# Arduino_MEGA_2560-Rev3.net
KiCad netlist of a schematic drawn in Altium Designer
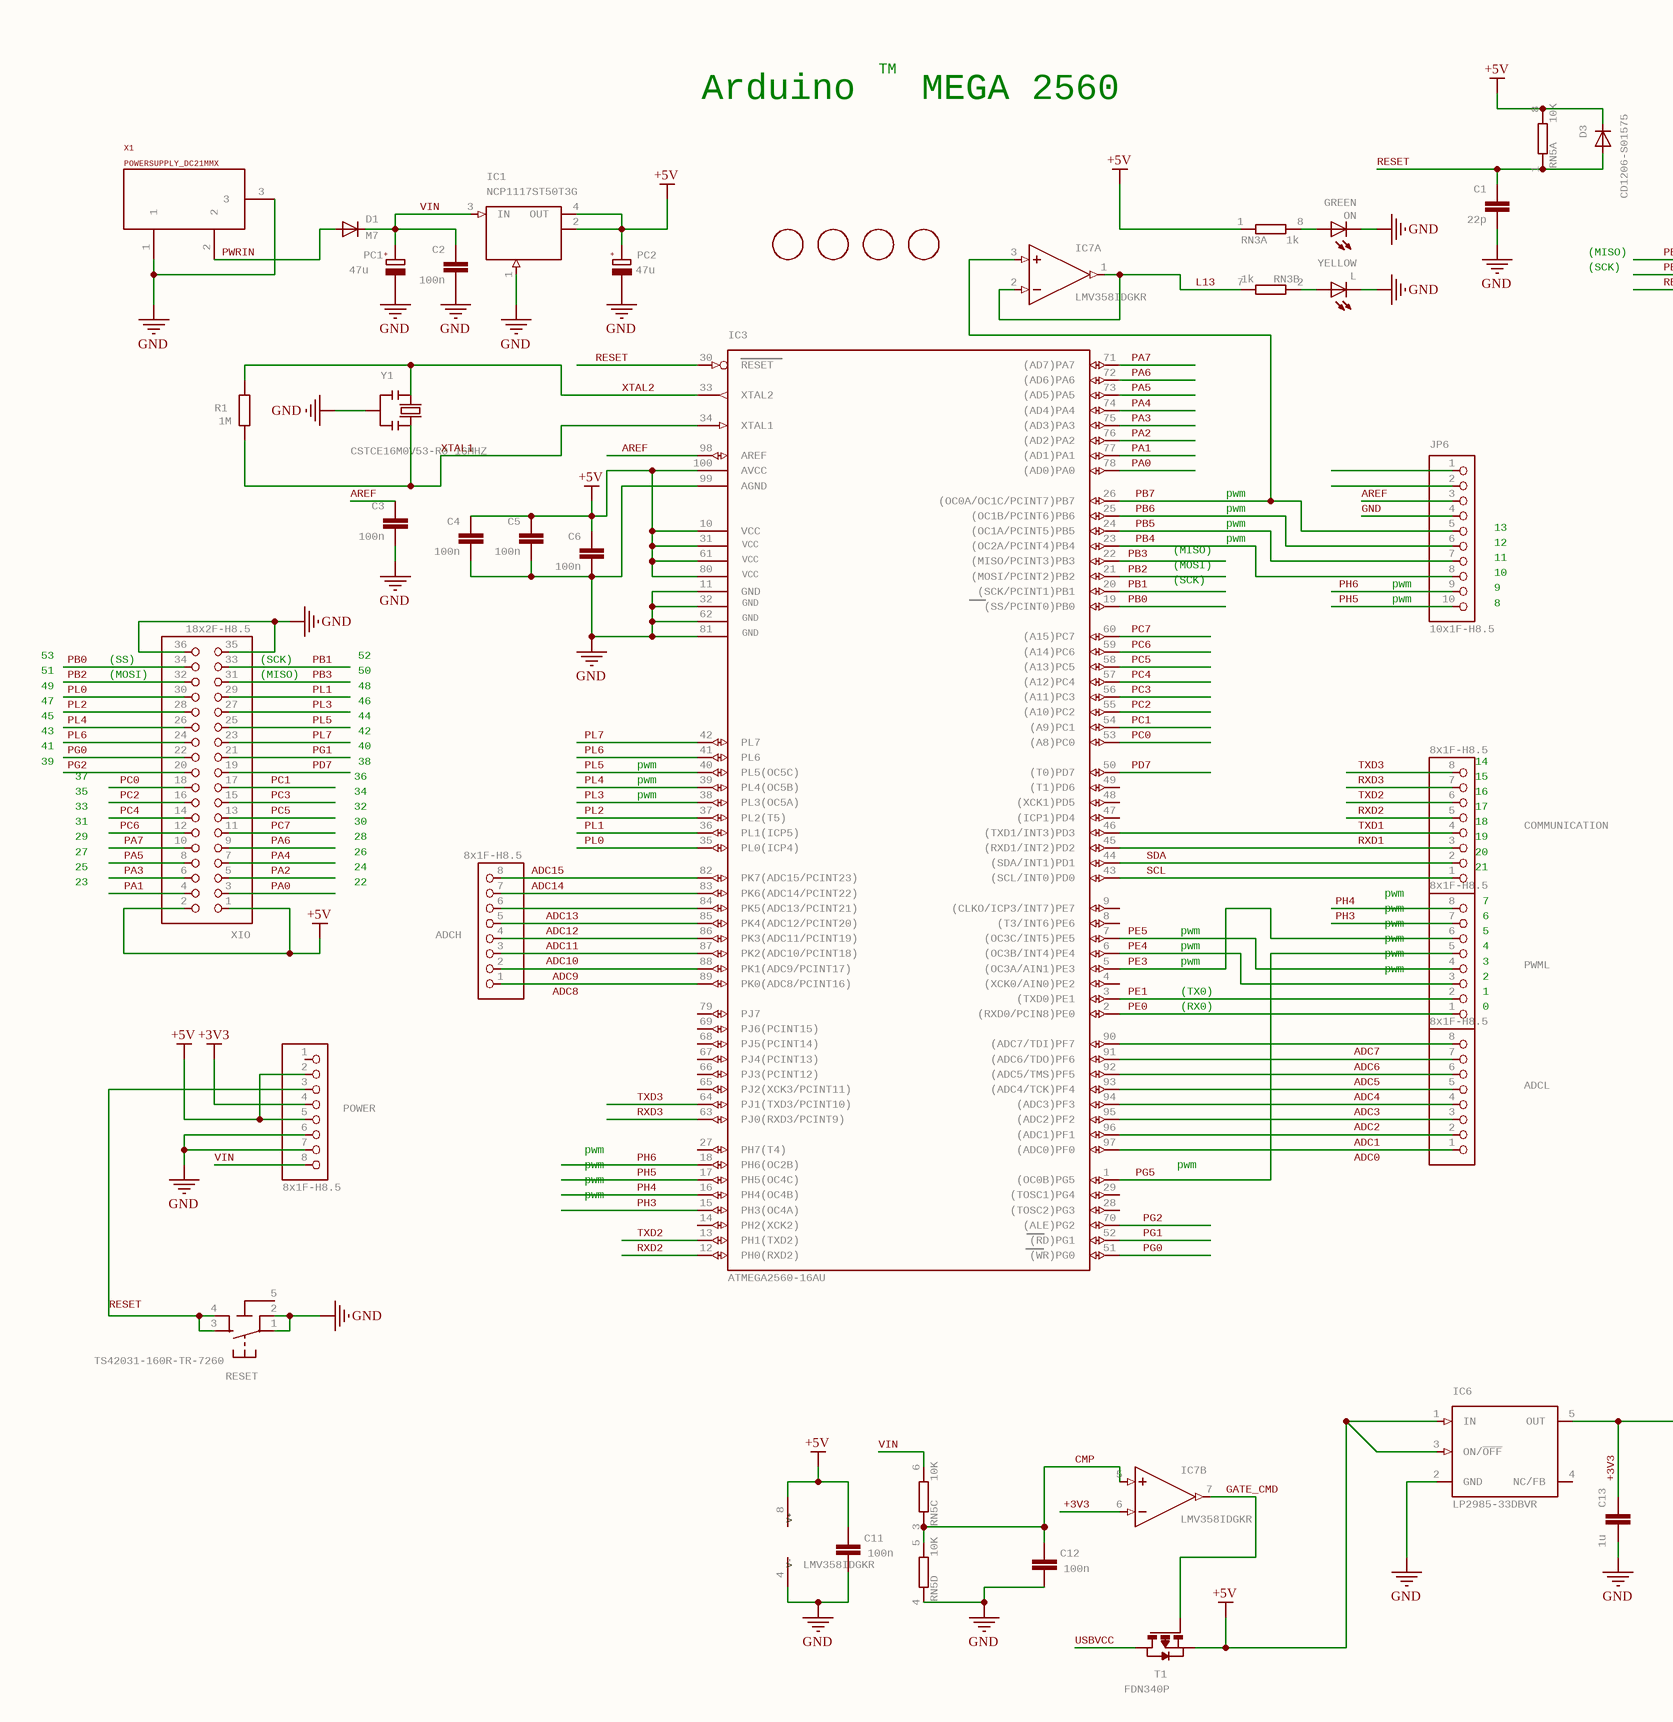
[diagram p0: Arduino_MEGA_2560-Rev3.SchDoc, left]
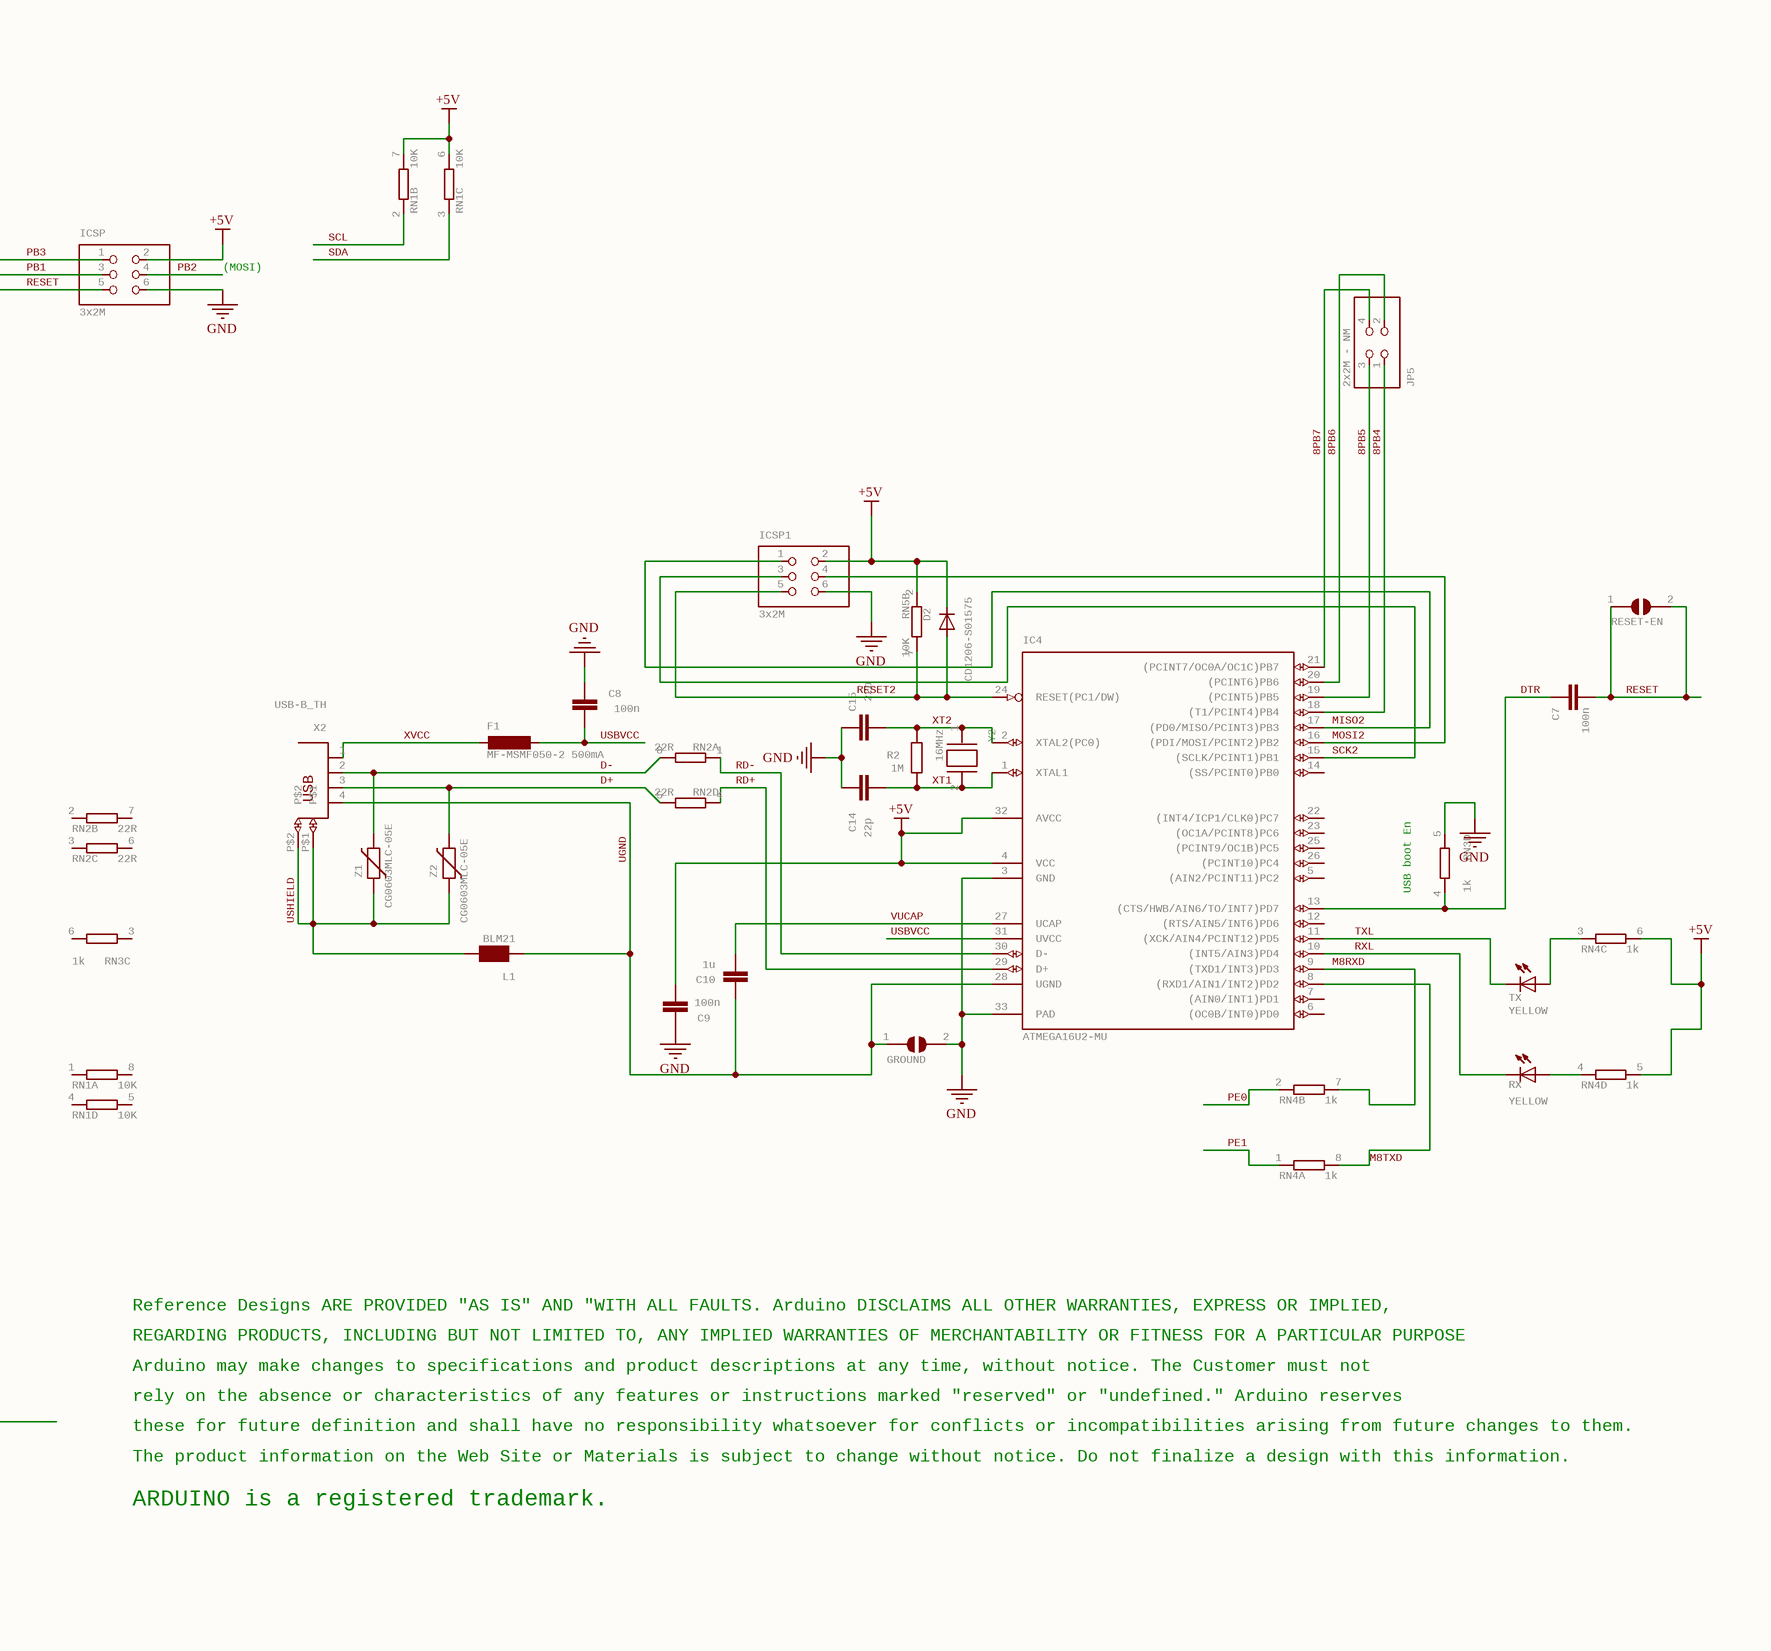
[diagram p1: Arduino_MEGA_2560-Rev3.SchDoc, right]

(export (version "E")
  (design (tool "Eeschema 10.0.6"))
  (components
    (comp (ref "ADCH")
      (value "8x1F-H8.5")
      (footprint "1X08")
      (description "PIN HEADER")
      (libsource (lib "SmartPrj") (part "PINHD-1X8"))
    )
    (comp (ref "ADCL")
      (value "8x1F-H8.5")
      (footprint "1X08")
      (description "PIN HEADER")
      (libsource (lib "SmartPrj") (part "PINHD-1X8"))
    )
    (comp (ref "C1")
      (value "22p")
      (footprint "C0603-ROUND")
      (description "CAPACITOR, European symbol")
      (libsource (lib "SmartPrj") (part "C-EU0603-RND"))
    )
    (comp (ref "C2")
      (value "100n")
      (footprint "C0603-ROUND")
      (description "CAPACITOR, European symbol")
      (libsource (lib "SmartPrj") (part "C-EU0603-RND"))
    )
    (comp (ref "C3")
      (value "100n")
      (footprint "C0603-ROUND")
      (description "CAPACITOR, European symbol")
      (libsource (lib "SmartPrj") (part "C-EU0603-RND"))
    )
    (comp (ref "C4")
      (value "100n")
      (footprint "C0603-ROUND")
      (description "CAPACITOR, European symbol")
      (libsource (lib "SmartPrj") (part "C-EU0603-RND"))
    )
    (comp (ref "C5")
      (value "100n")
      (footprint "C0603-ROUND")
      (description "CAPACITOR, European symbol")
      (libsource (lib "SmartPrj") (part "C-EU0603-RND"))
    )
    (comp (ref "C6")
      (value "100n")
      (footprint "C0603-ROUND")
      (description "CAPACITOR, European symbol")
      (libsource (lib "SmartPrj") (part "C-EU0603-RND"))
    )
    (comp (ref "C7")
      (value "100n")
      (footprint "C0603-ROUND")
      (description "CAPACITOR, European symbol")
      (libsource (lib "") (part "C-EU0603-RND_3"))
    )
    (comp (ref "C8")
      (value "100n")
      (footprint "C0603-ROUND")
      (description "CAPACITOR, European symbol")
      (libsource (lib "") (part "C-EU0603-RND_3"))
    )
    (comp (ref "C9")
      (value "100n")
      (footprint "C0603-ROUND")
      (description "CAPACITOR, European symbol")
      (libsource (lib "") (part "C-EU0603-RND_2"))
    )
    (comp (ref "C10")
      (value "1u")
      (footprint "C0603-ROUND")
      (description "CAPACITOR, European symbol")
      (libsource (lib "SmartPrj") (part "C-EU0603-RND"))
    )
    (comp (ref "C11")
      (value "100n")
      (footprint "C0603-ROUND")
      (description "CAPACITOR, European symbol")
      (libsource (lib "") (part "C-EU0603-RND_1"))
    )
    (comp (ref "C12")
      (value "100n")
      (footprint "C0603-ROUND")
      (description "CAPACITOR, European symbol")
      (libsource (lib "") (part "C-EU0603-RND_1"))
    )
    (comp (ref "C13")
      (value "1u")
      (footprint "C0603-ROUND")
      (description "CAPACITOR, European symbol")
      (libsource (lib "") (part "C-EU0603-RND_3"))
    )
    (comp (ref "C14")
      (value "22p")
      (footprint "C0603-ROUND")
      (description "CAPACITOR, European symbol")
      (libsource (lib "") (part "C-EU0603-RND_2"))
    )
    (comp (ref "C15")
      (value "22p")
      (footprint "C0603-ROUND")
      (description "CAPACITOR, European symbol")
      (libsource (lib "") (part "C-EU0603-RND_2"))
    )
    (comp (ref "COMMUNICATION")
      (value "8x1F-H8.5")
      (footprint "1X08")
      (description "PIN HEADER")
      (libsource (lib "SmartPrj") (part "PINHD-1X8"))
    )
    (comp (ref "D1")
      (value "M7")
      (footprint "SMB")
      (description "DIODE")
      (libsource (lib "diode") (part "DIODE-SMB"))
    )
    (comp (ref "D2")
      (value "CD1206-S01575")
      (footprint "MINIMELF")
      (description "DIODE")
      (libsource (lib "diode") (part "DIODE-MINIMELF"))
    )
    (comp (ref "D3")
      (value "CD1206-S01575")
      (footprint "MINIMELF")
      (description "DIODE")
      (libsource (lib "diode") (part "DIODE-MINIMELF"))
    )
    (comp (ref "F1")
      (value "MF-MSMF050-2 500mA")
      (footprint "L1812")
      (description "INDUCTOR, European symbol")
      (libsource (lib "rcl") (part "L-EUL1812"))
    )
    (comp (ref "FD1")
      (value "FIDUCIALMOUNT")
      (footprint "FIDUCIA-MOUNT")
      (libsource (lib "SmartPrj") (part "FIDUCIALMOUNT"))
    )
    (comp (ref "FD2")
      (value "FIDUCIALMOUNT")
      (footprint "FIDUCIA-MOUNT")
      (libsource (lib "SmartPrj") (part "FIDUCIALMOUNT"))
    )
    (comp (ref "FD3")
      (value "FIDUCIALMOUNT")
      (footprint "FIDUCIA-MOUNT")
      (libsource (lib "SmartPrj") (part "FIDUCIALMOUNT"))
    )
    (comp (ref "FD4")
      (value "FIDUCIALMOUNT")
      (footprint "FIDUCIA-MOUNT")
      (libsource (lib "SmartPrj") (part "FIDUCIALMOUNT"))
    )
    (comp (ref "GROUND")
      (value "SJ")
      (footprint "SJ")
      (description "SMD solder JUMPER")
      (libsource (lib "jumper") (part "SJ"))
    )
    (comp (ref "IC1")
      (value "NCP1117ST50T3G")
      (footprint "SOT223")
      (libsource (lib "linear") (part "MC33269ST*"))
    )
    (comp (ref "IC3")
      (value "ATMEGA2560-16AU")
      (footprint "TQFP100")
      (fields
        (field (name "GND") "GND")
        (field (name "GND_1") "GND")
        (field (name "GND_2") "GND")
        (field (name "VCC") "VCC")
        (field (name "VCC_1") "VCC")
        (field (name "VCC_2") "VCC")
      )
      (libsource (lib "SmartPrj") (part "ATMEGA2560AU"))
    )
    (comp (ref "IC4")
      (value "ATMEGA16U2-MU")
      (footprint "MLF32")
      (libsource (lib "SmartPrj") (part "ATMEGA16U2-MU"))
    )
    (comp (ref "IC6")
      (value "LP2985-33DBVR")
      (footprint "SOT23-DBV")
      (libsource (lib "SmartPrj") (part "LP2985-XXDBVR"))
    )
    (comp (ref "IC7")
      (value "LMV358IDGKR")
      (footprint "MSOP08")
      (fields (field (name "V+") "V+") (field (name "V-") "V-"))
      (libsource (lib "linear") (part "LMV358?*MM"))
    )
    (comp (ref "ICSP")
      (value "3x2M")
      (footprint "2X03")
      (description "PIN HEADER")
      (libsource (lib "SmartPrj") (part "PINHD-2X3"))
    )
    (comp (ref "ICSP1")
      (value "3x2M")
      (footprint "2X03")
      (description "PIN HEADER")
      (libsource (lib "SmartPrj") (part "PINHD-2X3"))
    )
    (comp (ref "JP5")
      (value "2x2M - NM")
      (footprint "2X02")
      (description "PIN HEADER")
      (libsource (lib "SmartPrj") (part "PINHD-2X2"))
    )
    (comp (ref "JP6")
      (value "10x1F-H8.5")
      (footprint "1X10")
      (description "PIN HEADER")
      (libsource (lib "SmartPrj") (part "PINHD-1X10_ARD"))
    )
    (comp (ref "L")
      (value "YELLOW")
      (footprint "CHIP-LED0805")
      (libsource (lib "led") (part "LEDCHIP-LED0805"))
    )
    (comp (ref "L1")
      (value "BLM21")
      (footprint "0805")
      (libsource (lib "wuerth-elektronik") (part "WE-CBF_0805"))
    )
    (comp (ref "ON")
      (value "GREEN")
      (footprint "CHIP-LED0805")
      (libsource (lib "led") (part "LEDCHIP-LED0805"))
    )
    (comp (ref "PC1")
      (value "47u")
      (footprint "PANASONIC_D")
      (description "POLARIZED CAPACITOR, European symbol")
      (fields (field (name "+") "+"))
      (libsource (lib "rcl") (part "CPOL-EUD"))
    )
    (comp (ref "PC2")
      (value "47u")
      (footprint "PANASONIC_D")
      (description "POLARIZED CAPACITOR, European symbol")
      (fields (field (name "+") "+"))
      (libsource (lib "rcl") (part "CPOL-EUD"))
    )
    (comp (ref "POWER")
      (value "8x1F-H8.5")
      (footprint "1X08")
      (description "PIN HEADER")
      (libsource (lib "SmartPrj") (part "PINHD-1X8"))
    )
    (comp (ref "PWML")
      (value "8x1F-H8.5")
      (footprint "1X08")
      (description "PIN HEADER")
      (libsource (lib "SmartPrj") (part "PINHD-1X8"))
    )
    (comp (ref "R1")
      (value "1M")
      (footprint "R0603-ROUND")
      (description "RESISTOR, European symbol")
      (libsource (lib "SmartPrj") (part "R-EU_R0603"))
    )
    (comp (ref "R2")
      (value "1M")
      (footprint "R0603-ROUND")
      (description "RESISTOR, European symbol")
      (libsource (lib "SmartPrj") (part "R-EU_R0603"))
    )
    (comp (ref "RESET")
      (value "TS42031-160R-TR-7260")
      (footprint "TS42")
      (description "TS42 Dongnan Electronics Tact switch VDC 12V - 50mA")
      (libsource (lib "SmartPrj") (part "TS42"))
    )
    (comp (ref "RESET-EN")
      (value "SJ")
      (footprint "SJ")
      (description "SMD solder JUMPER")
      (libsource (lib "jumper") (part "SJ"))
    )
    (comp (ref "RN1")
      (value "10K")
      (footprint "CAT16")
      (description "Array Chip Resistor   Source: RS Component / Phycomp")
      (fields (field (name "LIBRARYNAME") "resistor-dil"))
      (libsource (lib "resistor-dil") (part "4R-NCAT16"))
    )
    (comp (ref "RN2")
      (value "22R")
      (footprint "CAY16")
      (description "Array Chip Resistor   Source: RS Component / Phycomp")
      (fields (field (name "LIBRARYNAME") "resistor-dil"))
      (libsource (lib "resistor-dil") (part "4R-NCAY16"))
    )
    (comp (ref "RN3")
      (value "1k")
      (footprint "CAY16")
      (description "Array Chip Resistor   Source: RS Component / Phycomp")
      (fields (field (name "LIBRARYNAME") "resistor-dil"))
      (libsource (lib "resistor-dil") (part "4R-NCAY16"))
    )
    (comp (ref "RN4")
      (value "1k")
      (footprint "CAY16")
      (description "Array Chip Resistor   Source: RS Component / Phycomp")
      (fields (field (name "LIBRARYNAME") "resistor-dil"))
      (libsource (lib "resistor-dil") (part "4R-NCAY16"))
    )
    (comp (ref "RN5")
      (value "10K")
      (footprint "CAT16")
      (description "Array Chip Resistor   Source: RS Component / Phycomp")
      (fields (field (name "LIBRARYNAME") "resistor-dil"))
      (libsource (lib "resistor-dil") (part "4R-NCAT16"))
    )
    (comp (ref "RX")
      (value "YELLOW")
      (footprint "CHIP-LED0805")
      (libsource (lib "led") (part "LEDCHIP-LED0805"))
    )
    (comp (ref "T1")
      (value "FDN340P")
      (footprint "SOT-23")
      (description "MOS FET")
      (libsource (lib "zetex") (part "PMOSSOT23"))
    )
    (comp (ref "TX")
      (value "YELLOW")
      (footprint "CHIP-LED0805")
      (libsource (lib "led") (part "LEDCHIP-LED0805"))
    )
    (comp (ref "U$1")
      (value "DISCLAIMER")
      (footprint "DISCLAIMER")
      (fields
        (field (name "REFERENCEDESIGNSAREPROVIDED\"ASIS\"AND\"WITHALLFAULTS.ARDUINODISCLAIMSALLOTHERWARRANTIES,EXPRESSORIMPLIED,") "Reference Designs ARE PROVIDED \"AS IS\" AND \"WITH ALL FAULTS. Arduino DISCLAIMS ALL OTHER WARRANTIES, EXPRESS OR IMPLIED,")
        (field (name "ARDUINOMAYMAKECHANGESTOSPECIFICATIONSANDPRODUCTDESCRIPTIONSATANYTIME,WITHOUTNOTICE.THECUSTOMERMUSTNOT") "Arduino may make changes to specifications and product descriptions at any time, without notice. The Customer must not")
        (field (name "REGARDINGPRODUCTS,INCLUDINGBUTNOTLIMITEDTO,ANYIMPLIEDWARRANTIESOFMERCHANTABILITYORFITNESSFORAPARTICULARPURPOSE") "REGARDING PRODUCTS, INCLUDING BUT NOT LIMITED TO, ANY IMPLIED WARRANTIES OF MERCHANTABILITY OR FITNESS FOR A PARTICULAR PURPOSE")
        (field (name "RELYONTHEABSENCEORCHARACTERISTICSOFANYFEATURESORINSTRUCTIONSMARKED\"RESERVED\"OR\"UNDEFINED.\"ARDUINORESERVES") "rely on the absence or characteristics of any features or instructions marked \"reserved\" or \"undefined.\" Arduino reserves")
        (field (name "THESEFORFUTUREDEFINITIONANDSHALLHAVENORESPONSIBILITYWHATSOEVERFORCONFLICTSORINCOMPATIBILITIESARISINGFROMFUTURECHANGESTOTHEM.") "these for future definition and shall have no responsibility whatsoever for conflicts or incompatibilities arising from future changes to them.")
        (field (name "THEPRODUCTINFORMATIONONTHEWEBSITEORMATERIALSISSUBJECTTOCHANGEWITHOUTNOTICE.DONOTFINALIZEADESIGNWITHTHISINFORMATION.") "The product information on the Web Site or Materials is subject to change without notice. Do not finalize a design with this information.")
        (field (name "ARDUINOISAREGISTEREDTRADEMARK.") "ARDUINO is a registered trademark.")
      )
      (libsource (lib "SmartPrj") (part "DISCLAIMER"))
    )
    (comp (ref "X1")
      (value "POWERSUPPLY_DC21MMX")
      (footprint "POWERSUPPLY_DC-21MM")
      (libsource (lib "SmartPrj") (part "POWERSUPPLY_DC21MMX"))
    )
    (comp (ref "X2")
      (value "USB-B_TH")
      (footprint "PN61729")
      (description "BERG USB connector")
      (fields (field (name "USB") "USB"))
      (libsource (lib "SmartPrj") (part "PN61729"))
    )
    (comp (ref "XIO")
      (value "18x2F-H8.5")
      (footprint "2X18")
      (description "PIN HEADER")
      (libsource (lib "SmartPrj") (part "PINHD-2X18"))
    )
    (comp (ref "Y1")
      (value "CSTCE16M0V53-R0 16MHZ")
      (footprint "RESONATOR")
      (libsource (lib "SmartPrj") (part "RESONATORMU"))
    )
    (comp (ref "Y2")
      (value "16MHz")
      (footprint "QS")
      (description "CRYSTAL")
      (libsource (lib "SmartPrj") (part "XTAL/S"))
    )
    (comp (ref "Z1")
      (value "CG0603MLC-05E")
      (footprint "CT/CN0603")
      (description "VARISTOR")
      (libsource (lib "varistor") (part "VARISTORCN0603"))
    )
    (comp (ref "Z2")
      (value "CG0603MLC-05E")
      (footprint "CT/CN0603")
      (description "VARISTOR")
      (libsource (lib "varistor") (part "VARISTORCN0603"))
    )
  )
  (nets
    (net (code "1") (name "+3V3") (class "Default")
      (node (ref "C13") (pin "2") (pinfunction "2_2") (pintype "passive"))
      (node (ref "IC6") (pin "5") (pinfunction "OUT_5") (pintype "passive"))
      (node (ref "IC7") (pin "6") (pinfunction "-IN_6") (pintype "input"))
      (node (ref "POWER") (pin "4") (pinfunction "4_4") (pintype "passive"))
    )
    (net (code "2") (name "+5V") (class "Default")
      (node (ref "C11") (pin "2") (pinfunction "2_2") (pintype "passive"))
      (node (ref "C4") (pin "1") (pinfunction "1_1") (pintype "passive"))
      (node (ref "C5") (pin "1") (pinfunction "1_1") (pintype "passive"))
      (node (ref "C6") (pin "1") (pinfunction "1_1") (pintype "passive"))
      (node (ref "C9") (pin "1") (pinfunction "1_1") (pintype "passive"))
      (node (ref "D2") (pin "C") (pinfunction "C_C") (pintype "passive"))
      (node (ref "D3") (pin "C") (pinfunction "C_C") (pintype "passive"))
      (node (ref "IC1") (pin "2") (pinfunction "OUT_2") (pintype "passive"))
      (node (ref "IC1") (pin "4") (pinfunction "OUT_4") (pintype "passive"))
      (node (ref "IC3") (pin "10") (pinfunction "VCC_10") (pintype "power_in"))
      (node (ref "IC3") (pin "100") (pinfunction "AVCC_100") (pintype "power_in"))
      (node (ref "IC3") (pin "31") (pinfunction "VCC1_31") (pintype "power_in"))
      (node (ref "IC3") (pin "61") (pinfunction "VCC2_61") (pintype "power_in"))
      (node (ref "IC3") (pin "80") (pinfunction "VCC3_80") (pintype "power_in"))
      (node (ref "IC4") (pin "32") (pinfunction "AVCC_32") (pintype "power_in"))
      (node (ref "IC4") (pin "4") (pinfunction "VCC_4") (pintype "power_in"))
      (node (ref "IC6") (pin "1") (pinfunction "IN_1") (pintype "input"))
      (node (ref "IC6") (pin "3") (pinfunction "ON/~{OFF}_3") (pintype "input"))
      (node (ref "IC7") (pin "8") (pinfunction "V+_8") (pintype "power_in"))
      (node (ref "ICSP") (pin "2") (pinfunction "2_2") (pintype "passive"))
      (node (ref "ICSP1") (pin "2") (pinfunction "2_2") (pintype "passive"))
      (node (ref "PC2") (pin "+") (pinfunction "+_+") (pintype "passive"))
      (node (ref "POWER") (pin "2") (pinfunction "2_2") (pintype "passive"))
      (node (ref "POWER") (pin "5") (pinfunction "5_5") (pintype "passive"))
      (node (ref "RN1") (pin "6") (pinfunction "2_6") (pintype "passive"))
      (node (ref "RN1") (pin "7") (pinfunction "2_7") (pintype "passive"))
      (node (ref "RN3") (pin "1") (pinfunction "1_1") (pintype "passive"))
      (node (ref "RN4") (pin "5") (pinfunction "2_5") (pintype "passive"))
      (node (ref "RN4") (pin "6") (pinfunction "2_6") (pintype "passive"))
      (node (ref "RN5") (pin "2") (pinfunction "1_2") (pintype "passive"))
      (node (ref "RN5") (pin "8") (pinfunction "2_8") (pintype "passive"))
      (node (ref "T1") (pin "2") (pinfunction "S_2") (pintype "passive"))
      (node (ref "XIO") (pin "1") (pinfunction "1_1") (pintype "passive"))
      (node (ref "XIO") (pin "2") (pinfunction "2_2") (pintype "passive"))
    )
    (net (code "3") (name "/8PB4") (class "Default")
      (node (ref "IC4") (pin "18") (pinfunction "(T1/PCINT4)PB4_18") (pintype "bidirectional"))
      (node (ref "JP5") (pin "1") (pinfunction "1_1") (pintype "passive"))
    )
    (net (code "4") (name "/8PB5") (class "Default")
      (node (ref "IC4") (pin "19") (pinfunction "(PCINT5)PB5_19") (pintype "bidirectional"))
      (node (ref "JP5") (pin "3") (pinfunction "3_3") (pintype "passive"))
    )
    (net (code "5") (name "/8PB6") (class "Default")
      (node (ref "IC4") (pin "20") (pinfunction "(PCINT6)PB6_20") (pintype "bidirectional"))
      (node (ref "JP5") (pin "2") (pinfunction "2_2") (pintype "passive"))
    )
    (net (code "6") (name "/8PB7") (class "Default")
      (node (ref "IC4") (pin "21") (pinfunction "(PCINT7/OC0A/OC1C)PB7_21") (pintype "bidirectional"))
      (node (ref "JP5") (pin "4") (pinfunction "4_4") (pintype "passive"))
    )
    (net (code "7") (name "/ADC0") (class "Default")
      (node (ref "ADCL") (pin "1") (pinfunction "1_1") (pintype "passive"))
      (node (ref "IC3") (pin "97") (pinfunction "(ADC0)PF0_97") (pintype "bidirectional"))
    )
    (net (code "8") (name "/ADC1") (class "Default")
      (node (ref "ADCL") (pin "2") (pinfunction "2_2") (pintype "passive"))
      (node (ref "IC3") (pin "96") (pinfunction "(ADC1)PF1_96") (pintype "bidirectional"))
    )
    (net (code "9") (name "/ADC2") (class "Default")
      (node (ref "ADCL") (pin "3") (pinfunction "3_3") (pintype "passive"))
      (node (ref "IC3") (pin "95") (pinfunction "(ADC2)PF2_95") (pintype "bidirectional"))
    )
    (net (code "10") (name "/ADC3") (class "Default")
      (node (ref "ADCL") (pin "4") (pinfunction "4_4") (pintype "passive"))
      (node (ref "IC3") (pin "94") (pinfunction "(ADC3)PF3_94") (pintype "bidirectional"))
    )
    (net (code "11") (name "/ADC4") (class "Default")
      (node (ref "ADCL") (pin "5") (pinfunction "5_5") (pintype "passive"))
      (node (ref "IC3") (pin "93") (pinfunction "(ADC4/TCK)PF4_93") (pintype "bidirectional"))
    )
    (net (code "12") (name "/ADC5") (class "Default")
      (node (ref "ADCL") (pin "6") (pinfunction "6_6") (pintype "passive"))
      (node (ref "IC3") (pin "92") (pinfunction "(ADC5/TMS)PF5_92") (pintype "bidirectional"))
    )
    (net (code "13") (name "/ADC6") (class "Default")
      (node (ref "ADCL") (pin "7") (pinfunction "7_7") (pintype "passive"))
      (node (ref "IC3") (pin "91") (pinfunction "(ADC6/TDO)PF6_91") (pintype "bidirectional"))
    )
    (net (code "14") (name "/ADC7") (class "Default")
      (node (ref "ADCL") (pin "8") (pinfunction "8_8") (pintype "passive"))
      (node (ref "IC3") (pin "90") (pinfunction "(ADC7/TDI)PF7_90") (pintype "bidirectional"))
    )
    (net (code "15") (name "/ADC8") (class "Default")
      (node (ref "ADCH") (pin "1") (pinfunction "1_1") (pintype "passive"))
      (node (ref "IC3") (pin "89") (pinfunction "PK0(ADC8/PCINT16)_89") (pintype "bidirectional"))
    )
    (net (code "16") (name "/ADC9") (class "Default")
      (node (ref "ADCH") (pin "2") (pinfunction "2_2") (pintype "passive"))
      (node (ref "IC3") (pin "88") (pinfunction "PK1(ADC9/PCINT17)_88") (pintype "bidirectional"))
    )
    (net (code "17") (name "/ADC10") (class "Default")
      (node (ref "ADCH") (pin "3") (pinfunction "3_3") (pintype "passive"))
      (node (ref "IC3") (pin "87") (pinfunction "PK2(ADC10/PCINT18)_87") (pintype "bidirectional"))
    )
    (net (code "18") (name "/ADC11") (class "Default")
      (node (ref "ADCH") (pin "4") (pinfunction "4_4") (pintype "passive"))
      (node (ref "IC3") (pin "86") (pinfunction "PK3(ADC11/PCINT19)_86") (pintype "bidirectional"))
    )
    (net (code "19") (name "/ADC12") (class "Default")
      (node (ref "ADCH") (pin "5") (pinfunction "5_5") (pintype "passive"))
      (node (ref "IC3") (pin "85") (pinfunction "PK4(ADC12/PCINT20)_85") (pintype "bidirectional"))
    )
    (net (code "20") (name "/ADC13") (class "Default")
      (node (ref "ADCH") (pin "6") (pinfunction "6_6") (pintype "passive"))
      (node (ref "IC3") (pin "84") (pinfunction "PK5(ADC13/PCINT21)_84") (pintype "bidirectional"))
    )
    (net (code "21") (name "/ADC14") (class "Default")
      (node (ref "ADCH") (pin "7") (pinfunction "7_7") (pintype "passive"))
      (node (ref "IC3") (pin "83") (pinfunction "PK6(ADC14/PCINT22)_83") (pintype "bidirectional"))
    )
    (net (code "22") (name "/ADC15") (class "Default")
      (node (ref "ADCH") (pin "8") (pinfunction "8_8") (pintype "passive"))
      (node (ref "IC3") (pin "82") (pinfunction "PK7(ADC15/PCINT23)_82") (pintype "bidirectional"))
    )
    (net (code "23") (name "/AREF") (class "Default")
      (node (ref "C3") (pin "1") (pinfunction "1_1") (pintype "passive"))
      (node (ref "IC3") (pin "98") (pinfunction "AREF_98") (pintype "bidirectional"))
      (node (ref "JP6") (pin "3") (pinfunction "3_3") (pintype "passive"))
    )
    (net (code "24") (name "/CMP") (class "Default")
      (node (ref "C12") (pin "2") (pinfunction "2_2") (pintype "passive"))
      (node (ref "IC7") (pin "5") (pinfunction "+IN_5") (pintype "input"))
      (node (ref "RN5") (pin "3") (pinfunction "1_3") (pintype "passive"))
      (node (ref "RN5") (pin "5") (pinfunction "2_5") (pintype "passive"))
    )
    (net (code "25") (name "/D+") (class "Default")
      (node (ref "RN2") (pin "5") (pinfunction "2_5") (pintype "passive"))
      (node (ref "X2") (pin "3") (pinfunction "3_3") (pintype "bidirectional"))
      (node (ref "Z2") (pin "2") (pinfunction "2_2") (pintype "passive"))
    )
    (net (code "26") (name "/D-") (class "Default")
      (node (ref "RN2") (pin "8") (pinfunction "2_8") (pintype "passive"))
      (node (ref "X2") (pin "2") (pinfunction "2_2") (pintype "bidirectional"))
      (node (ref "Z1") (pin "2") (pinfunction "2_2") (pintype "passive"))
    )
    (net (code "27") (name "/DTR") (class "Default")
      (node (ref "C7") (pin "1") (pinfunction "1_1") (pintype "passive"))
      (node (ref "IC4") (pin "13") (pinfunction "(CTS/HWB/AIN6/TO/INT7)PD7_13") (pintype "bidirectional"))
      (node (ref "RN3") (pin "4") (pinfunction "1_4") (pintype "passive"))
    )
    (net (code "28") (name "/GATE_CMD") (class "Default")
      (node (ref "IC7") (pin "7") (pinfunction "OUT_7") (pintype "output"))
      (node (ref "T1") (pin "3") (pinfunction "G_3") (pintype "passive"))
    )
    (net (code "29") (name "/L13") (class "Default")
      (node (ref "IC7") (pin "1") (pinfunction "OUT_1") (pintype "output"))
      (node (ref "IC7") (pin "2") (pinfunction "-IN_2") (pintype "input"))
      (node (ref "RN3") (pin "7") (pinfunction "2_7") (pintype "passive"))
    )
    (net (code "30") (name "/M8RXD") (class "Default")
      (node (ref "IC4") (pin "9") (pinfunction "(TXD1/INT3)PD3_9") (pintype "bidirectional"))
      (node (ref "RN4") (pin "7") (pinfunction "2_7") (pintype "passive"))
    )
    (net (code "31") (name "/M8TXD") (class "Default")
      (node (ref "IC4") (pin "8") (pinfunction "(RXD1/AIN1/INT2)PD2_8") (pintype "bidirectional"))
      (node (ref "RN4") (pin "8") (pinfunction "2_8") (pintype "passive"))
    )
    (net (code "32") (name "/MISO2") (class "Default")
      (node (ref "IC4") (pin "17") (pinfunction "(PD0/MISO/PCINT3)PB3_17") (pintype "bidirectional"))
      (node (ref "ICSP1") (pin "1") (pinfunction "1_1") (pintype "passive"))
    )
    (net (code "33") (name "/MOSI2") (class "Default")
      (node (ref "IC4") (pin "16") (pinfunction "(PDI/MOSI/PCINT2)PB2_16") (pintype "bidirectional"))
      (node (ref "ICSP1") (pin "4") (pinfunction "4_4") (pintype "passive"))
    )
    (net (code "34") (name "/PA0") (class "Default")
      (node (ref "IC3") (pin "78") (pinfunction "(AD0)PA0_78") (pintype "bidirectional"))
      (node (ref "XIO") (pin "3") (pinfunction "3_3") (pintype "passive"))
    )
    (net (code "35") (name "/PA1") (class "Default")
      (node (ref "IC3") (pin "77") (pinfunction "(AD1)PA1_77") (pintype "bidirectional"))
      (node (ref "XIO") (pin "4") (pinfunction "4_4") (pintype "passive"))
    )
    (net (code "36") (name "/PA2") (class "Default")
      (node (ref "IC3") (pin "76") (pinfunction "(AD2)PA2_76") (pintype "bidirectional"))
      (node (ref "XIO") (pin "5") (pinfunction "5_5") (pintype "passive"))
    )
    (net (code "37") (name "/PA3") (class "Default")
      (node (ref "IC3") (pin "75") (pinfunction "(AD3)PA3_75") (pintype "bidirectional"))
      (node (ref "XIO") (pin "6") (pinfunction "6_6") (pintype "passive"))
    )
    (net (code "38") (name "/PA4") (class "Default")
      (node (ref "IC3") (pin "74") (pinfunction "(AD4)PA4_74") (pintype "bidirectional"))
      (node (ref "XIO") (pin "7") (pinfunction "7_7") (pintype "passive"))
    )
    (net (code "39") (name "/PA5") (class "Default")
      (node (ref "IC3") (pin "73") (pinfunction "(AD5)PA5_73") (pintype "bidirectional"))
      (node (ref "XIO") (pin "8") (pinfunction "8_8") (pintype "passive"))
    )
    (net (code "40") (name "/PA6") (class "Default")
      (node (ref "IC3") (pin "72") (pinfunction "(AD6)PA6_72") (pintype "bidirectional"))
      (node (ref "XIO") (pin "9") (pinfunction "9_9") (pintype "passive"))
    )
    (net (code "41") (name "/PA7") (class "Default")
      (node (ref "IC3") (pin "71") (pinfunction "(AD7)PA7_71") (pintype "bidirectional"))
      (node (ref "XIO") (pin "10") (pinfunction "10_10") (pintype "passive"))
    )
    (net (code "42") (name "/PB0") (class "Default")
      (node (ref "IC3") (pin "19") (pinfunction "(SS/PCINT0)PB0_19") (pintype "bidirectional"))
      (node (ref "XIO") (pin "34") (pinfunction "34_34") (pintype "passive"))
    )
    (net (code "43") (name "/PB1") (class "Default")
      (node (ref "IC3") (pin "20") (pinfunction "(SCK/PCINT1)PB1_20") (pintype "bidirectional"))
      (node (ref "ICSP") (pin "3") (pinfunction "3_3") (pintype "passive"))
      (node (ref "XIO") (pin "33") (pinfunction "33_33") (pintype "passive"))
    )
    (net (code "44") (name "/PB2") (class "Default")
      (node (ref "IC3") (pin "21") (pinfunction "(MOSI/PCINT2)PB2_21") (pintype "bidirectional"))
      (node (ref "ICSP") (pin "4") (pinfunction "4_4") (pintype "passive"))
      (node (ref "XIO") (pin "32") (pinfunction "32_32") (pintype "passive"))
    )
    (net (code "45") (name "/PB3") (class "Default")
      (node (ref "IC3") (pin "22") (pinfunction "(MISO/PCINT3)PB3_22") (pintype "bidirectional"))
      (node (ref "ICSP") (pin "1") (pinfunction "1_1") (pintype "passive"))
      (node (ref "XIO") (pin "31") (pinfunction "31_31") (pintype "passive"))
    )
    (net (code "46") (name "/PB4") (class "Default")
      (node (ref "IC3") (pin "23") (pinfunction "(OC2A/PCINT4)PB4_23") (pintype "bidirectional"))
      (node (ref "JP6") (pin "8") (pinfunction "8_8") (pintype "passive"))
    )
    (net (code "47") (name "/PB5") (class "Default")
      (node (ref "IC3") (pin "24") (pinfunction "(OC1A/PCINT5)PB5_24") (pintype "bidirectional"))
      (node (ref "JP6") (pin "7") (pinfunction "7_7") (pintype "passive"))
    )
    (net (code "48") (name "/PB6") (class "Default")
      (node (ref "IC3") (pin "25") (pinfunction "(OC1B/PCINT6)PB6_25") (pintype "bidirectional"))
      (node (ref "JP6") (pin "6") (pinfunction "6_6") (pintype "passive"))
    )
    (net (code "49") (name "/PB7") (class "Default")
      (node (ref "IC3") (pin "26") (pinfunction "(OC0A/OC1C/PCINT7)PB7_26") (pintype "bidirectional"))
      (node (ref "IC7") (pin "3") (pinfunction "+IN_3") (pintype "input"))
      (node (ref "JP6") (pin "5") (pinfunction "5_5") (pintype "passive"))
    )
    (net (code "50") (name "/PC0") (class "Default")
      (node (ref "IC3") (pin "53") (pinfunction "(A8)PC0_53") (pintype "bidirectional"))
      (node (ref "XIO") (pin "18") (pinfunction "18_18") (pintype "passive"))
    )
    (net (code "51") (name "/PC1") (class "Default")
      (node (ref "IC3") (pin "54") (pinfunction "(A9)PC1_54") (pintype "bidirectional"))
      (node (ref "XIO") (pin "17") (pinfunction "17_17") (pintype "passive"))
    )
    (net (code "52") (name "/PC2") (class "Default")
      (node (ref "IC3") (pin "55") (pinfunction "(A10)PC2_55") (pintype "bidirectional"))
      (node (ref "XIO") (pin "16") (pinfunction "16_16") (pintype "passive"))
    )
    (net (code "53") (name "/PC3") (class "Default")
      (node (ref "IC3") (pin "56") (pinfunction "(A11)PC3_56") (pintype "bidirectional"))
      (node (ref "XIO") (pin "15") (pinfunction "15_15") (pintype "passive"))
    )
    (net (code "54") (name "/PC4") (class "Default")
      (node (ref "IC3") (pin "57") (pinfunction "(A12)PC4_57") (pintype "bidirectional"))
      (node (ref "XIO") (pin "14") (pinfunction "14_14") (pintype "passive"))
    )
    (net (code "55") (name "/PC5") (class "Default")
      (node (ref "IC3") (pin "58") (pinfunction "(A13)PC5_58") (pintype "bidirectional"))
      (node (ref "XIO") (pin "13") (pinfunction "13_13") (pintype "passive"))
    )
    (net (code "56") (name "/PC6") (class "Default")
      (node (ref "IC3") (pin "59") (pinfunction "(A14)PC6_59") (pintype "bidirectional"))
      (node (ref "XIO") (pin "12") (pinfunction "12_12") (pintype "passive"))
    )
    (net (code "57") (name "/PC7") (class "Default")
      (node (ref "IC3") (pin "60") (pinfunction "(A15)PC7_60") (pintype "bidirectional"))
      (node (ref "XIO") (pin "11") (pinfunction "11_11") (pintype "passive"))
    )
    (net (code "58") (name "/PD7") (class "Default")
      (node (ref "IC3") (pin "50") (pinfunction "(T0)PD7_50") (pintype "bidirectional"))
      (node (ref "XIO") (pin "19") (pinfunction "19_19") (pintype "passive"))
    )
    (net (code "59") (name "/PE0") (class "Default")
      (node (ref "IC3") (pin "2") (pinfunction "(RXD0/PCIN8)PE0_2") (pintype "bidirectional"))
      (node (ref "PWML") (pin "1") (pinfunction "1_1") (pintype "passive"))
      (node (ref "RN4") (pin "2") (pinfunction "1_2") (pintype "passive"))
    )
    (net (code "60") (name "/PE1") (class "Default")
      (node (ref "IC3") (pin "3") (pinfunction "(TXD0)PE1_3") (pintype "bidirectional"))
      (node (ref "PWML") (pin "2") (pinfunction "2_2") (pintype "passive"))
      (node (ref "RN4") (pin "1") (pinfunction "1_1") (pintype "passive"))
    )
    (net (code "61") (name "/PE3") (class "Default")
      (node (ref "IC3") (pin "5") (pinfunction "(OC3A/AIN1)PE3_5") (pintype "bidirectional"))
      (node (ref "PWML") (pin "6") (pinfunction "6_6") (pintype "passive"))
    )
    (net (code "62") (name "/PE4") (class "Default")
      (node (ref "IC3") (pin "6") (pinfunction "(OC3B/INT4)PE4_6") (pintype "bidirectional"))
      (node (ref "PWML") (pin "3") (pinfunction "3_3") (pintype "passive"))
    )
    (net (code "63") (name "/PE5") (class "Default")
      (node (ref "IC3") (pin "7") (pinfunction "(OC3C/INT5)PE5_7") (pintype "bidirectional"))
      (node (ref "PWML") (pin "4") (pinfunction "4_4") (pintype "passive"))
    )
    (net (code "64") (name "/PG0") (class "Default")
      (node (ref "IC3") (pin "51") (pinfunction "(WR)PG0_51") (pintype "bidirectional"))
      (node (ref "XIO") (pin "22") (pinfunction "22_22") (pintype "passive"))
    )
    (net (code "65") (name "/PG1") (class "Default")
      (node (ref "IC3") (pin "52") (pinfunction "(RD)PG1_52") (pintype "bidirectional"))
      (node (ref "XIO") (pin "21") (pinfunction "21_21") (pintype "passive"))
    )
    (net (code "66") (name "/PG2") (class "Default")
      (node (ref "IC3") (pin "70") (pinfunction "(ALE)PG2_70") (pintype "bidirectional"))
      (node (ref "XIO") (pin "20") (pinfunction "20_20") (pintype "passive"))
    )
    (net (code "67") (name "/PG5") (class "Default")
      (node (ref "IC3") (pin "1") (pinfunction "(OC0B)PG5_1") (pintype "bidirectional"))
      (node (ref "PWML") (pin "5") (pinfunction "5_5") (pintype "passive"))
    )
    (net (code "68") (name "/PH3") (class "Default")
      (node (ref "IC3") (pin "15") (pinfunction "PH3(OC4A)_15") (pintype "bidirectional"))
      (node (ref "PWML") (pin "7") (pinfunction "7_7") (pintype "passive"))
    )
    (net (code "69") (name "/PH4") (class "Default")
      (node (ref "IC3") (pin "16") (pinfunction "PH4(OC4B)_16") (pintype "bidirectional"))
      (node (ref "PWML") (pin "8") (pinfunction "8_8") (pintype "passive"))
    )
    (net (code "70") (name "/PH5") (class "Default")
      (node (ref "IC3") (pin "17") (pinfunction "PH5(OC4C)_17") (pintype "bidirectional"))
      (node (ref "JP6") (pin "10") (pinfunction "10_10") (pintype "passive"))
    )
    (net (code "71") (name "/PH6") (class "Default")
      (node (ref "IC3") (pin "18") (pinfunction "PH6(OC2B)_18") (pintype "bidirectional"))
      (node (ref "JP6") (pin "9") (pinfunction "9_9") (pintype "passive"))
    )
    (net (code "72") (name "/PL0") (class "Default")
      (node (ref "IC3") (pin "35") (pinfunction "PL0(ICP4)_35") (pintype "bidirectional"))
      (node (ref "XIO") (pin "30") (pinfunction "30_30") (pintype "passive"))
    )
    (net (code "73") (name "/PL1") (class "Default")
      (node (ref "IC3") (pin "36") (pinfunction "PL1(ICP5)_36") (pintype "bidirectional"))
      (node (ref "XIO") (pin "29") (pinfunction "29_29") (pintype "passive"))
    )
    (net (code "74") (name "/PL2") (class "Default")
      (node (ref "IC3") (pin "37") (pinfunction "PL2(T5)_37") (pintype "bidirectional"))
      (node (ref "XIO") (pin "28") (pinfunction "28_28") (pintype "passive"))
    )
    (net (code "75") (name "/PL3") (class "Default")
      (node (ref "IC3") (pin "38") (pinfunction "PL3(OC5A)_38") (pintype "bidirectional"))
      (node (ref "XIO") (pin "27") (pinfunction "27_27") (pintype "passive"))
    )
    (net (code "76") (name "/PL4") (class "Default")
      (node (ref "IC3") (pin "39") (pinfunction "PL4(OC5B)_39") (pintype "bidirectional"))
      (node (ref "XIO") (pin "26") (pinfunction "26_26") (pintype "passive"))
    )
    (net (code "77") (name "/PL5") (class "Default")
      (node (ref "IC3") (pin "40") (pinfunction "PL5(OC5C)_40") (pintype "bidirectional"))
      (node (ref "XIO") (pin "25") (pinfunction "25_25") (pintype "passive"))
    )
    (net (code "78") (name "/PL6") (class "Default")
      (node (ref "IC3") (pin "41") (pinfunction "PL6_41") (pintype "bidirectional"))
      (node (ref "XIO") (pin "24") (pinfunction "24_24") (pintype "passive"))
    )
    (net (code "79") (name "/PL7") (class "Default")
      (node (ref "IC3") (pin "42") (pinfunction "PL7_42") (pintype "bidirectional"))
      (node (ref "XIO") (pin "23") (pinfunction "23_23") (pintype "passive"))
    )
    (net (code "80") (name "/PWRIN") (class "Default")
      (node (ref "D1") (pin "A") (pinfunction "A_A") (pintype "passive"))
      (node (ref "X1") (pin "2") (pinfunction "2_2") (pintype "power_in"))
    )
    (net (code "81") (name "/RD+") (class "Default")
      (node (ref "IC4") (pin "29") (pinfunction "D+_29") (pintype "bidirectional"))
      (node (ref "RN2") (pin "4") (pinfunction "1_4") (pintype "passive"))
    )
    (net (code "82") (name "/RD-") (class "Default")
      (node (ref "IC4") (pin "30") (pinfunction "D-_30") (pintype "bidirectional"))
      (node (ref "RN2") (pin "1") (pinfunction "1_1") (pintype "passive"))
    )
    (net (code "83") (name "/RESET") (class "Default")
      (node (ref "C1") (pin "1") (pinfunction "1_1") (pintype "passive"))
      (node (ref "C7") (pin "2") (pinfunction "2_2") (pintype "passive"))
      (node (ref "D3") (pin "A") (pinfunction "A_A") (pintype "passive"))
      (node (ref "IC3") (pin "30") (pinfunction "RESET_30") (pintype "input"))
      (node (ref "ICSP") (pin "5") (pinfunction "5_5") (pintype "passive"))
      (node (ref "POWER") (pin "3") (pinfunction "3_3") (pintype "passive"))
      (node (ref "RESET") (pin "3") (pinfunction "3_3") (pintype "passive"))
      (node (ref "RESET") (pin "4") (pinfunction "4_4") (pintype "passive"))
      (node (ref "RESET-EN") (pin "1") (pinfunction "1_1") (pintype "passive"))
      (node (ref "RESET-EN") (pin "2") (pinfunction "2_2") (pintype "passive"))
      (node (ref "RN5") (pin "1") (pinfunction "1_1") (pintype "passive"))
    )
    (net (code "84") (name "/RESET2") (class "Default")
      (node (ref "D2") (pin "A") (pinfunction "A_A") (pintype "passive"))
      (node (ref "IC4") (pin "24") (pinfunction "RESET(PC1/DW)_24") (pintype "input"))
      (node (ref "ICSP1") (pin "5") (pinfunction "5_5") (pintype "passive"))
      (node (ref "RN5") (pin "7") (pinfunction "2_7") (pintype "passive"))
    )
    (net (code "85") (name "/RXD1") (class "Default")
      (node (ref "COMMUNICATION") (pin "3") (pinfunction "3_3") (pintype "passive"))
      (node (ref "IC3") (pin "45") (pinfunction "(RXD1/INT2)PD2_45") (pintype "bidirectional"))
    )
    (net (code "86") (name "/RXD2") (class "Default")
      (node (ref "COMMUNICATION") (pin "5") (pinfunction "5_5") (pintype "passive"))
      (node (ref "IC3") (pin "12") (pinfunction "PH0(RXD2)_12") (pintype "bidirectional"))
    )
    (net (code "87") (name "/RXD3") (class "Default")
      (node (ref "COMMUNICATION") (pin "7") (pinfunction "7_7") (pintype "passive"))
      (node (ref "IC3") (pin "63") (pinfunction "PJ0(RXD3/PCINT9)_63") (pintype "bidirectional"))
    )
    (net (code "88") (name "/RXL") (class "Default")
      (node (ref "IC4") (pin "10") (pinfunction "(INT5/AIN3)PD4_10") (pintype "bidirectional"))
      (node (ref "RX") (pin "C") (pinfunction "C_C") (pintype "passive"))
    )
    (net (code "89") (name "/SCK2") (class "Default")
      (node (ref "IC4") (pin "15") (pinfunction "(SCLK/PCINT1)PB1_15") (pintype "bidirectional"))
      (node (ref "ICSP1") (pin "3") (pinfunction "3_3") (pintype "passive"))
    )
    (net (code "90") (name "/SCL") (class "Default")
      (node (ref "COMMUNICATION") (pin "1") (pinfunction "1_1") (pintype "passive"))
      (node (ref "IC3") (pin "43") (pinfunction "(SCL/INT0)PD0_43") (pintype "bidirectional"))
      (node (ref "RN1") (pin "2") (pinfunction "1_2") (pintype "passive"))
    )
    (net (code "91") (name "/SDA") (class "Default")
      (node (ref "COMMUNICATION") (pin "2") (pinfunction "2_2") (pintype "passive"))
      (node (ref "IC3") (pin "44") (pinfunction "(SDA/INT1)PD1_44") (pintype "bidirectional"))
      (node (ref "RN1") (pin "3") (pinfunction "1_3") (pintype "passive"))
    )
    (net (code "92") (name "/TXD1") (class "Default")
      (node (ref "COMMUNICATION") (pin "4") (pinfunction "4_4") (pintype "passive"))
      (node (ref "IC3") (pin "46") (pinfunction "(TXD1/INT3)PD3_46") (pintype "bidirectional"))
    )
    (net (code "93") (name "/TXD2") (class "Default")
      (node (ref "COMMUNICATION") (pin "6") (pinfunction "6_6") (pintype "passive"))
      (node (ref "IC3") (pin "13") (pinfunction "PH1(TXD2)_13") (pintype "bidirectional"))
    )
    (net (code "94") (name "/TXD3") (class "Default")
      (node (ref "COMMUNICATION") (pin "8") (pinfunction "8_8") (pintype "passive"))
      (node (ref "IC3") (pin "64") (pinfunction "PJ1(TXD3/PCINT10)_64") (pintype "bidirectional"))
    )
    (net (code "95") (name "/TXL") (class "Default")
      (node (ref "IC4") (pin "11") (pinfunction "(XCK/AIN4/PCINT12)PD5_11") (pintype "bidirectional"))
      (node (ref "TX") (pin "C") (pinfunction "C_C") (pintype "passive"))
    )
    (net (code "96") (name "/UGND") (class "Default")
      (node (ref "C10") (pin "2") (pinfunction "2_2") (pintype "passive"))
      (node (ref "GROUND") (pin "1") (pinfunction "1_1") (pintype "passive"))
      (node (ref "IC4") (pin "28") (pinfunction "UGND_28") (pintype "power_in"))
      (node (ref "L1") (pin "1") (pinfunction "1_1") (pintype "passive"))
      (node (ref "X2") (pin "4") (pinfunction "4_4") (pintype "bidirectional"))
    )
    (net (code "97") (name "/USBVCC") (class "Default")
      (node (ref "C8") (pin "1") (pinfunction "1_1") (pintype "passive"))
      (node (ref "F1") (pin "1") (pinfunction "1_1") (pintype "passive"))
      (node (ref "IC4") (pin "31") (pinfunction "UVCC_31") (pintype "power_in"))
      (node (ref "T1") (pin "1") (pinfunction "D_1") (pintype "passive"))
    )
    (net (code "98") (name "/USHIELD") (class "Default")
      (node (ref "L1") (pin "2") (pinfunction "2_2") (pintype "passive"))
      (node (ref "X2") (pin "P$1") (pinfunction "P$1_P$1") (pintype "bidirectional"))
      (node (ref "X2") (pin "P$2") (pinfunction "P$2_P$2") (pintype "bidirectional"))
      (node (ref "Z1") (pin "1") (pinfunction "1_1") (pintype "passive"))
      (node (ref "Z2") (pin "1") (pinfunction "1_1") (pintype "passive"))
    )
    (net (code "99") (name "/VIN") (class "Default")
      (node (ref "C2") (pin "1") (pinfunction "1_1") (pintype "passive"))
      (node (ref "D1") (pin "C") (pinfunction "C_C") (pintype "passive"))
      (node (ref "IC1") (pin "3") (pinfunction "IN_3") (pintype "input"))
      (node (ref "PC1") (pin "+") (pinfunction "+_+") (pintype "passive"))
      (node (ref "POWER") (pin "8") (pinfunction "8_8") (pintype "passive"))
      (node (ref "RN5") (pin "6") (pinfunction "2_6") (pintype "passive"))
    )
    (net (code "100") (name "/VUCAP") (class "Default")
      (node (ref "C10") (pin "1") (pinfunction "1_1") (pintype "passive"))
      (node (ref "IC4") (pin "27") (pinfunction "UCAP_27") (pintype "passive"))
    )
    (net (code "101") (name "/XT1") (class "Default")
      (node (ref "C14") (pin "1") (pinfunction "1_1") (pintype "passive"))
      (node (ref "IC4") (pin "1") (pinfunction "XTAL1_1") (pintype "bidirectional"))
      (node (ref "R2") (pin "1") (pinfunction "1_1") (pintype "passive"))
      (node (ref "Y2") (pin "2") (pinfunction "2_2") (pintype "passive"))
    )
    (net (code "102") (name "/XT2") (class "Default")
      (node (ref "C15") (pin "1") (pinfunction "1_1") (pintype "passive"))
      (node (ref "IC4") (pin "2") (pinfunction "XTAL2(PC0)_2") (pintype "bidirectional"))
      (node (ref "R2") (pin "2") (pinfunction "2_2") (pintype "passive"))
      (node (ref "Y2") (pin "1") (pinfunction "1_1") (pintype "passive"))
    )
    (net (code "103") (name "/XTAL1") (class "Default")
      (node (ref "IC3") (pin "34") (pinfunction "XTAL1_34") (pintype "input"))
      (node (ref "R1") (pin "1") (pinfunction "1_1") (pintype "passive"))
      (node (ref "Y1") (pin "3") (pinfunction "3_3") (pintype "passive"))
    )
    (net (code "104") (name "/XTAL2") (class "Default")
      (node (ref "IC3") (pin "33") (pinfunction "XTAL2_33") (pintype "output"))
      (node (ref "R1") (pin "2") (pinfunction "2_2") (pintype "passive"))
      (node (ref "Y1") (pin "1") (pinfunction "1_1") (pintype "passive"))
    )
    (net (code "105") (name "/XVCC") (class "Default")
      (node (ref "F1") (pin "2") (pinfunction "2_2") (pintype "passive"))
      (node (ref "X2") (pin "1") (pinfunction "1_1") (pintype "bidirectional"))
    )
    (net (code "106") (name "GND") (class "Default")
      (node (ref "C1") (pin "2") (pinfunction "2_2") (pintype "passive"))
      (node (ref "C11") (pin "1") (pinfunction "1_1") (pintype "passive"))
      (node (ref "C12") (pin "1") (pinfunction "1_1") (pintype "passive"))
      (node (ref "C13") (pin "1") (pinfunction "1_1") (pintype "passive"))
      (node (ref "C14") (pin "2") (pinfunction "2_2") (pintype "passive"))
      (node (ref "C15") (pin "2") (pinfunction "2_2") (pintype "passive"))
      (node (ref "C2") (pin "2") (pinfunction "2_2") (pintype "passive"))
      (node (ref "C3") (pin "2") (pinfunction "2_2") (pintype "passive"))
      (node (ref "C4") (pin "2") (pinfunction "2_2") (pintype "passive"))
      (node (ref "C5") (pin "2") (pinfunction "2_2") (pintype "passive"))
      (node (ref "C6") (pin "2") (pinfunction "2_2") (pintype "passive"))
      (node (ref "C8") (pin "2") (pinfunction "2_2") (pintype "passive"))
      (node (ref "C9") (pin "2") (pinfunction "2_2") (pintype "passive"))
      (node (ref "GROUND") (pin "2") (pinfunction "2_2") (pintype "passive"))
      (node (ref "IC1") (pin "1") (pinfunction "GND/ADJ_1") (pintype "input"))
      (node (ref "IC3") (pin "11") (pinfunction "GND_11") (pintype "power_in"))
      (node (ref "IC3") (pin "32") (pinfunction "GND1_32") (pintype "power_in"))
      (node (ref "IC3") (pin "62") (pinfunction "GND2_62") (pintype "power_in"))
      (node (ref "IC3") (pin "81") (pinfunction "GND3_81") (pintype "power_in"))
      (node (ref "IC3") (pin "99") (pinfunction "AGND_99") (pintype "power_in"))
      (node (ref "IC4") (pin "3") (pinfunction "GND_3") (pintype "power_in"))
      (node (ref "IC4") (pin "33") (pinfunction "PAD_33") (pintype "power_in"))
      (node (ref "IC6") (pin "2") (pinfunction "GND_2") (pintype "power_in"))
      (node (ref "IC7") (pin "4") (pinfunction "V-_4") (pintype "power_in"))
      (node (ref "ICSP") (pin "6") (pinfunction "6_6") (pintype "passive"))
      (node (ref "ICSP1") (pin "6") (pinfunction "6_6") (pintype "passive"))
      (node (ref "JP6") (pin "4") (pinfunction "4_4") (pintype "passive"))
      (node (ref "L") (pin "C") (pinfunction "C_C") (pintype "passive"))
      (node (ref "ON") (pin "C") (pinfunction "C_C") (pintype "passive"))
      (node (ref "PC1") (pin "-") (pinfunction "-_-") (pintype "passive"))
      (node (ref "PC2") (pin "-") (pinfunction "-_-") (pintype "passive"))
      (node (ref "POWER") (pin "6") (pinfunction "6_6") (pintype "passive"))
      (node (ref "POWER") (pin "7") (pinfunction "7_7") (pintype "passive"))
      (node (ref "RESET") (pin "1") (pinfunction "1_1") (pintype "passive"))
      (node (ref "RESET") (pin "2") (pinfunction "2_2") (pintype "passive"))
      (node (ref "RN3") (pin "5") (pinfunction "2_5") (pintype "passive"))
      (node (ref "RN5") (pin "4") (pinfunction "1_4") (pintype "passive"))
      (node (ref "X1") (pin "1") (pinfunction "1_1") (pintype "power_in"))
      (node (ref "X1") (pin "3") (pinfunction "3_3") (pintype "power_in"))
      (node (ref "XIO") (pin "35") (pinfunction "35_35") (pintype "passive"))
      (node (ref "XIO") (pin "36") (pinfunction "36_36") (pintype "passive"))
      (node (ref "Y1") (pin "2") (pinfunction "2_2") (pintype "passive"))
    )
    (net (code "107") (name "Net-(RN3A-2)") (class "Default")
      (node (ref "ON") (pin "A") (pinfunction "A_A") (pintype "passive"))
      (node (ref "RN3") (pin "8") (pinfunction "2_8") (pintype "passive"))
    )
    (net (code "108") (name "Net-(RN3B-1)") (class "Default")
      (node (ref "L") (pin "A") (pinfunction "A_A") (pintype "passive"))
      (node (ref "RN3") (pin "2") (pinfunction "1_2") (pintype "passive"))
    )
    (net (code "109") (name "Net-(RN4C-1)") (class "Default")
      (node (ref "RN4") (pin "3") (pinfunction "1_3") (pintype "passive"))
      (node (ref "TX") (pin "A") (pinfunction "A_A") (pintype "passive"))
    )
    (net (code "110") (name "Net-(RN4D-1)") (class "Default")
      (node (ref "RN4") (pin "4") (pinfunction "1_4") (pintype "passive"))
      (node (ref "RX") (pin "A") (pinfunction "A_A") (pintype "passive"))
    )
    (net (code "111") (name "unconnected-(IC3-(CLKO{slash}ICP3{slash}INT7)PE7-Pad9)") (class "Default")
      (node (ref "IC3") (pin "9") (pinfunction "(CLKO/ICP3/INT7)PE7_9") (pintype "bidirectional"))
    )
    (net (code "112") (name "unconnected-(IC3-(ICP1)PD4-Pad47)") (class "Default")
      (node (ref "IC3") (pin "47") (pinfunction "(ICP1)PD4_47") (pintype "bidirectional"))
    )
    (net (code "113") (name "unconnected-(IC3-(T1)PD6-Pad49)") (class "Default")
      (node (ref "IC3") (pin "49") (pinfunction "(T1)PD6_49") (pintype "bidirectional"))
    )
    (net (code "114") (name "unconnected-(IC3-(T3{slash}INT6)PE6-Pad8)") (class "Default")
      (node (ref "IC3") (pin "8") (pinfunction "(T3/INT6)PE6_8") (pintype "bidirectional"))
    )
    (net (code "115") (name "unconnected-(IC3-(TOSC1)PG4-Pad29)") (class "Default")
      (node (ref "IC3") (pin "29") (pinfunction "(TOSC1)PG4_29") (pintype "bidirectional"))
    )
    (net (code "116") (name "unconnected-(IC3-(TOSC2)PG3-Pad28)") (class "Default")
      (node (ref "IC3") (pin "28") (pinfunction "(TOSC2)PG3_28") (pintype "bidirectional"))
    )
    (net (code "117") (name "unconnected-(IC3-(XCK0{slash}AIN0)PE2-Pad4)") (class "Default")
      (node (ref "IC3") (pin "4") (pinfunction "(XCK0/AIN0)PE2_4") (pintype "bidirectional"))
    )
    (net (code "118") (name "unconnected-(IC3-(XCK1)PD5-Pad48)") (class "Default")
      (node (ref "IC3") (pin "48") (pinfunction "(XCK1)PD5_48") (pintype "bidirectional"))
    )
    (net (code "119") (name "unconnected-(IC3-PH2(XCK2)-Pad14)") (class "Default")
      (node (ref "IC3") (pin "14") (pinfunction "PH2(XCK2)_14") (pintype "bidirectional"))
    )
    (net (code "120") (name "unconnected-(IC3-PH7(T4)-Pad27)") (class "Default")
      (node (ref "IC3") (pin "27") (pinfunction "PH7(T4)_27") (pintype "bidirectional"))
    )
    (net (code "121") (name "unconnected-(IC3-PJ2(XCK3{slash}PCINT11)-Pad65)") (class "Default")
      (node (ref "IC3") (pin "65") (pinfunction "PJ2(XCK3/PCINT11)_65") (pintype "bidirectional"))
    )
    (net (code "122") (name "unconnected-(IC3-PJ3(PCINT12)-Pad66)") (class "Default")
      (node (ref "IC3") (pin "66") (pinfunction "PJ3(PCINT12)_66") (pintype "bidirectional"))
    )
    (net (code "123") (name "unconnected-(IC3-PJ4(PCINT13)-Pad67)") (class "Default")
      (node (ref "IC3") (pin "67") (pinfunction "PJ4(PCINT13)_67") (pintype "bidirectional"))
    )
    (net (code "124") (name "unconnected-(IC3-PJ5(PCINT14)-Pad68)") (class "Default")
      (node (ref "IC3") (pin "68") (pinfunction "PJ5(PCINT14)_68") (pintype "bidirectional"))
    )
    (net (code "125") (name "unconnected-(IC3-PJ6(PCINT15)-Pad69)") (class "Default")
      (node (ref "IC3") (pin "69") (pinfunction "PJ6(PCINT15)_69") (pintype "bidirectional"))
    )
    (net (code "126") (name "unconnected-(IC3-PJ7-Pad79)") (class "Default")
      (node (ref "IC3") (pin "79") (pinfunction "PJ7_79") (pintype "bidirectional"))
    )
    (net (code "127") (name "unconnected-(IC4-(AIN0{slash}INT1)PD1-Pad7)") (class "Default")
      (node (ref "IC4") (pin "7") (pinfunction "(AIN0/INT1)PD1_7") (pintype "bidirectional"))
    )
    (net (code "128") (name "unconnected-(IC4-(AIN2{slash}PCINT11)PC2-Pad5)") (class "Default")
      (node (ref "IC4") (pin "5") (pinfunction "(AIN2/PCINT11)PC2_5") (pintype "bidirectional"))
    )
    (net (code "129") (name "unconnected-(IC4-(INT4{slash}ICP1{slash}CLK0)PC7-Pad22)") (class "Default")
      (node (ref "IC4") (pin "22") (pinfunction "(INT4/ICP1/CLK0)PC7_22") (pintype "bidirectional"))
    )
    (net (code "130") (name "unconnected-(IC4-(OC0B{slash}INT0)PD0-Pad6)") (class "Default")
      (node (ref "IC4") (pin "6") (pinfunction "(OC0B/INT0)PD0_6") (pintype "bidirectional"))
    )
    (net (code "131") (name "unconnected-(IC4-(OC1A{slash}PCINT8)PC6-Pad23)") (class "Default")
      (node (ref "IC4") (pin "23") (pinfunction "(OC1A/PCINT8)PC6_23") (pintype "bidirectional"))
    )
    (net (code "132") (name "unconnected-(IC4-(PCINT9{slash}OC1B)PC5-Pad25)") (class "Default")
      (node (ref "IC4") (pin "25") (pinfunction "(PCINT9/OC1B)PC5_25") (pintype "bidirectional"))
    )
    (net (code "133") (name "unconnected-(IC4-(PCINT10)PC4-Pad26)") (class "Default")
      (node (ref "IC4") (pin "26") (pinfunction "(PCINT10)PC4_26") (pintype "bidirectional"))
    )
    (net (code "134") (name "unconnected-(IC4-(RTS{slash}AIN5{slash}INT6)PD6-Pad12)") (class "Default")
      (node (ref "IC4") (pin "12") (pinfunction "(RTS/AIN5/INT6)PD6_12") (pintype "bidirectional"))
    )
    (net (code "135") (name "unconnected-(IC4-(SS{slash}PCINT0)PB0-Pad14)") (class "Default")
      (node (ref "IC4") (pin "14") (pinfunction "(SS/PCINT0)PB0_14") (pintype "bidirectional"))
    )
    (net (code "136") (name "unconnected-(IC6-NC{slash}FB-Pad4)") (class "Default")
      (node (ref "IC6") (pin "4") (pinfunction "NC/FB_4") (pintype "passive"))
    )
    (net (code "137") (name "unconnected-(JP6-Pad1)") (class "Default")
      (node (ref "JP6") (pin "1") (pinfunction "1_1") (pintype "passive"))
    )
    (net (code "138") (name "unconnected-(JP6-Pad2)") (class "Default")
      (node (ref "JP6") (pin "2") (pinfunction "2_2") (pintype "passive"))
    )
    (net (code "139") (name "unconnected-(POWER-Pad1)") (class "Default")
      (node (ref "POWER") (pin "1") (pinfunction "1_1") (pintype "passive"))
    )
    (net (code "140") (name "unconnected-(RESET-5-GND-Pad5)") (class "Default")
      (node (ref "RESET") (pin "5") (pinfunction "5-GND_5") (pintype "power_in"))
    )
    (net (code "141") (name "unconnected-(RN1-Pad1)") (class "Default")
      (node (ref "RN1") (pin "1") (pinfunction "1_1") (pintype "passive"))
    )
    (net (code "142") (name "unconnected-(RN1A-2-Pad8)") (class "Default")
      (node (ref "RN1") (pin "8") (pinfunction "2_8") (pintype "passive"))
    )
    (net (code "143") (name "unconnected-(RN1D-1-Pad4)") (class "Default")
      (node (ref "RN1") (pin "4") (pinfunction "1_4") (pintype "passive"))
    )
    (net (code "144") (name "unconnected-(RN1D-2-Pad5)") (class "Default")
      (node (ref "RN1") (pin "5") (pinfunction "2_5") (pintype "passive"))
    )
    (net (code "145") (name "unconnected-(RN2B-1-Pad2)") (class "Default")
      (node (ref "RN2") (pin "2") (pinfunction "1_2") (pintype "passive"))
    )
    (net (code "146") (name "unconnected-(RN2B-2-Pad7)") (class "Default")
      (node (ref "RN2") (pin "7") (pinfunction "2_7") (pintype "passive"))
    )
    (net (code "147") (name "unconnected-(RN2C-1-Pad3)") (class "Default")
      (node (ref "RN2") (pin "3") (pinfunction "1_3") (pintype "passive"))
    )
    (net (code "148") (name "unconnected-(RN2C-2-Pad6)") (class "Default")
      (node (ref "RN2") (pin "6") (pinfunction "2_6") (pintype "passive"))
    )
    (net (code "149") (name "unconnected-(RN3C-1-Pad3)") (class "Default")
      (node (ref "RN3") (pin "3") (pinfunction "1_3") (pintype "passive"))
    )
    (net (code "150") (name "unconnected-(RN3C-2-Pad6)") (class "Default")
      (node (ref "RN3") (pin "6") (pinfunction "2_6") (pintype "passive"))
    )
  )
)
